# ABC_proto.net
KiCad netlist of a schematic drawn in EAGLE
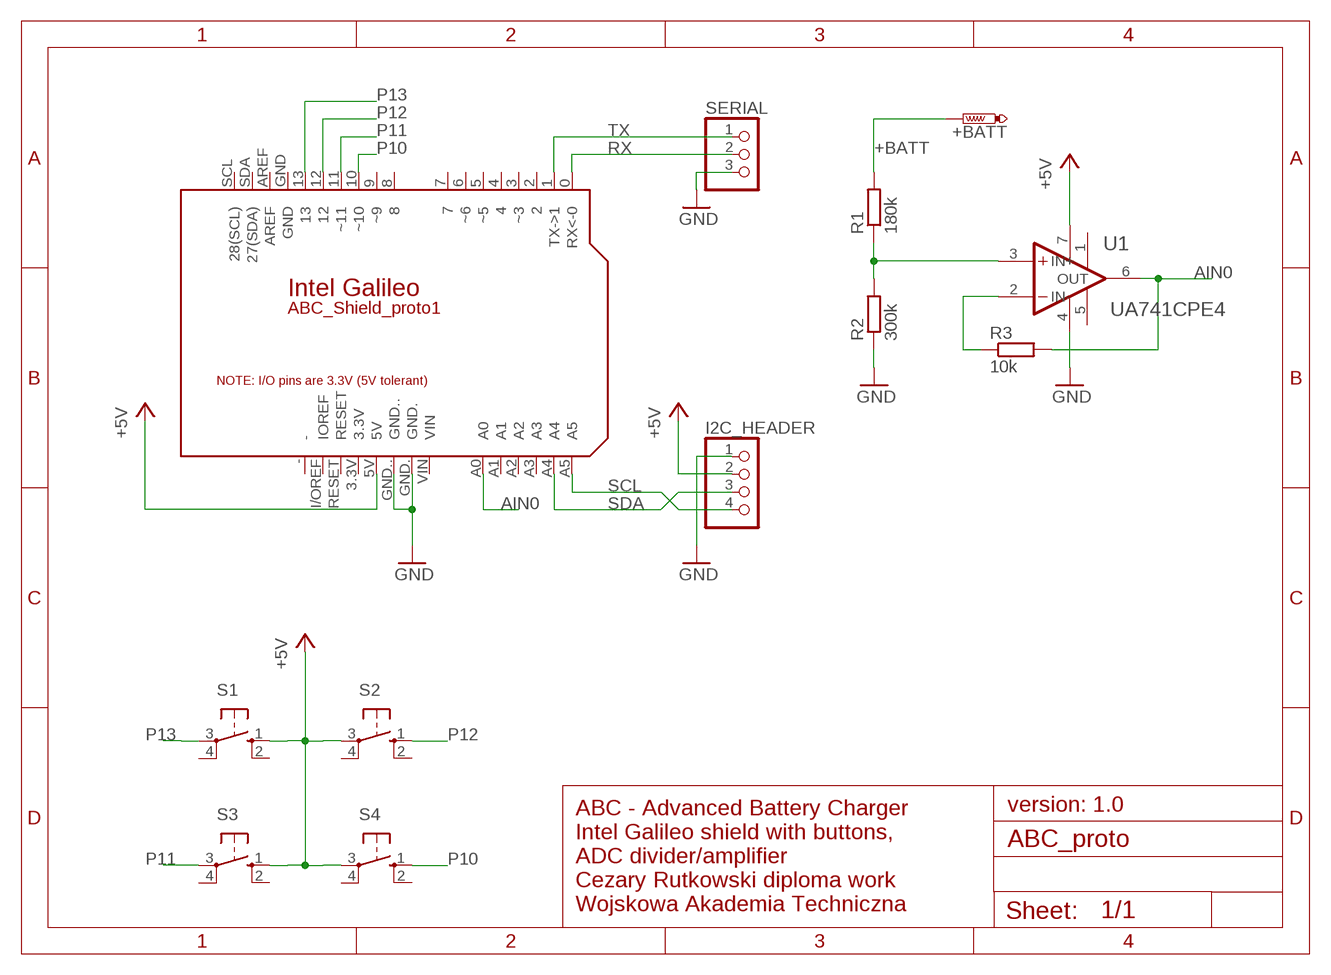
[diagram p0: schematic, sheet 1]

(export (version "E")
  (design (tool "Eeschema 10.0.6"))
  (components
    (comp (ref "+BATT")
      (value "PTR1PAD1-20Y")
      (footprint "eagle-import:P1-20Y")
      (libsource (lib "eagle-import") (part "PTR1PAD1-20Y"))
    )
    (comp (ref "I2C_HEADER")
      (value "PINHD-1X4")
      (footprint "eagle-import:1X04")
      (libsource (lib "eagle-import") (part "PINHD-1X4"))
    )
    (comp (ref "PCB1")
      (value "ARDUINO_101")
      (footprint "eagle-import:ARDUINO_GALILEO")
      (libsource (lib "eagle-import") (part "ARDUINO_101"))
    )
    (comp (ref "R1")
      (value "180k")
      (footprint "eagle-import:0204_5")
      (libsource (lib "eagle-import") (part "R-EU_0204/5"))
    )
    (comp (ref "R2")
      (value "300k")
      (footprint "eagle-import:0204_5")
      (libsource (lib "eagle-import") (part "R-EU_0204/5"))
    )
    (comp (ref "R3")
      (value "10k")
      (footprint "eagle-import:0204_5")
      (libsource (lib "eagle-import") (part "R-EU_0204/5"))
    )
    (comp (ref "S1")
      (value "10-XX")
      (footprint "eagle-import:B3F-10XX")
      (fields (field (name "MPN") "B3F-1000"))
      (libsource (lib "eagle-import") (part "10-XX"))
    )
    (comp (ref "S2")
      (value "10-XX")
      (footprint "eagle-import:B3F-10XX")
      (fields (field (name "MPN") "B3F-1000"))
      (libsource (lib "eagle-import") (part "10-XX"))
    )
    (comp (ref "S3")
      (value "10-XX")
      (footprint "eagle-import:B3F-10XX")
      (fields (field (name "MPN") "B3F-1000"))
      (libsource (lib "eagle-import") (part "10-XX"))
    )
    (comp (ref "S4")
      (value "10-XX")
      (footprint "eagle-import:B3F-10XX")
      (fields (field (name "MPN") "B3F-1000"))
      (libsource (lib "eagle-import") (part "10-XX"))
    )
    (comp (ref "SERIAL")
      (value "PINHD-1X3")
      (footprint "eagle-import:1X03")
      (libsource (lib "eagle-import") (part "PINHD-1X3"))
    )
    (comp (ref "U1")
      (value "UA741CPE4")
      (footprint "eagle-import:DIP254P762X508-8")
      (libsource (lib "eagle-import") (part "UA741CPE4"))
    )
  )
  (nets
    (net (code "1") (name "+5V") (class "Default")
      (node (ref "I2C_HEADER") (pin "2") (pinfunction "2_2") (pintype "passive"))
      (node (ref "PCB1") (pin "5V") (pinfunction "5V_5V") (pintype "bidirectional"))
      (node (ref "S1") (pin "1") (pinfunction "S_1") (pintype "passive"))
      (node (ref "S2") (pin "3") (pinfunction "P_3") (pintype "passive"))
      (node (ref "S3") (pin "1") (pinfunction "S_1") (pintype "passive"))
      (node (ref "S4") (pin "3") (pinfunction "P_3") (pintype "passive"))
      (node (ref "U1") (pin "7") (pinfunction "VCC+_7") (pintype "power_in"))
    )
    (net (code "2") (name "/+BATT") (class "Default")
      (node (ref "+BATT") (pin "TP") (pinfunction "TP_TP") (pintype "input"))
      (node (ref "R1") (pin "2") (pinfunction "2_2") (pintype "passive"))
    )
    (net (code "3") (name "/AIN0") (class "Default")
      (node (ref "PCB1") (pin "A0") (pinfunction "A0_A0") (pintype "bidirectional"))
      (node (ref "R3") (pin "2") (pinfunction "2_2") (pintype "passive"))
      (node (ref "U1") (pin "6") (pinfunction "OUT_6") (pintype "output"))
    )
    (net (code "4") (name "/P10") (class "Default")
      (node (ref "PCB1") (pin "10") (pinfunction "~{10}_10") (pintype "bidirectional"))
      (node (ref "S4") (pin "1") (pinfunction "S_1") (pintype "passive"))
    )
    (net (code "5") (name "/P11") (class "Default")
      (node (ref "PCB1") (pin "11") (pinfunction "~{11}_11") (pintype "bidirectional"))
      (node (ref "S3") (pin "3") (pinfunction "P_3") (pintype "passive"))
    )
    (net (code "6") (name "/P12") (class "Default")
      (node (ref "PCB1") (pin "12") (pinfunction "12_12") (pintype "bidirectional"))
      (node (ref "S2") (pin "1") (pinfunction "S_1") (pintype "passive"))
    )
    (net (code "7") (name "/P13") (class "Default")
      (node (ref "PCB1") (pin "13") (pinfunction "13_13") (pintype "bidirectional"))
      (node (ref "S1") (pin "3") (pinfunction "P_3") (pintype "passive"))
    )
    (net (code "8") (name "/RX") (class "Default")
      (node (ref "PCB1") (pin "0") (pinfunction "RX<-0_0") (pintype "bidirectional"))
      (node (ref "SERIAL") (pin "2") (pinfunction "2_2") (pintype "passive"))
    )
    (net (code "9") (name "/SCL") (class "Default")
      (node (ref "I2C_HEADER") (pin "4") (pinfunction "4_4") (pintype "passive"))
      (node (ref "PCB1") (pin "A5") (pinfunction "A5_A5") (pintype "bidirectional"))
    )
    (net (code "10") (name "/SDA") (class "Default")
      (node (ref "I2C_HEADER") (pin "3") (pinfunction "3_3") (pintype "passive"))
      (node (ref "PCB1") (pin "A4") (pinfunction "A4_A4") (pintype "bidirectional"))
    )
    (net (code "11") (name "/TX") (class "Default")
      (node (ref "PCB1") (pin "1") (pinfunction "TX->1_1") (pintype "bidirectional"))
      (node (ref "SERIAL") (pin "1") (pinfunction "1_1") (pintype "passive"))
    )
    (net (code "12") (name "GND") (class "Default")
      (node (ref "I2C_HEADER") (pin "1") (pinfunction "1_1") (pintype "passive"))
      (node (ref "PCB1") (pin "GND.") (pinfunction "GND._GND.") (pintype "bidirectional"))
      (node (ref "PCB1") (pin "GND..") (pinfunction "GND.._GND..") (pintype "bidirectional"))
      (node (ref "R2") (pin "1") (pinfunction "1_1") (pintype "passive"))
      (node (ref "SERIAL") (pin "3") (pinfunction "3_3") (pintype "passive"))
      (node (ref "U1") (pin "4") (pinfunction "VCC-_4") (pintype "power_in"))
    )
    (net (code "13") (name "Net-(U1-IN+)") (class "Default")
      (node (ref "R1") (pin "1") (pinfunction "1_1") (pintype "passive"))
      (node (ref "R2") (pin "2") (pinfunction "2_2") (pintype "passive"))
      (node (ref "U1") (pin "3") (pinfunction "IN+_3") (pintype "input"))
    )
    (net (code "14") (name "Net-(U1-IN-)") (class "Default")
      (node (ref "R3") (pin "1") (pinfunction "1_1") (pintype "passive"))
      (node (ref "U1") (pin "2") (pinfunction "IN-_2") (pintype "input"))
    )
    (net (code "15") (name "unconnected-(PCB1-27(SDA)-PadSDA)") (class "Default")
      (node (ref "PCB1") (pin "SDA") (pinfunction "27(SDA)_SDA") (pintype "bidirectional"))
    )
    (net (code "16") (name "unconnected-(PCB1-28(SCL)-PadSCL)") (class "Default")
      (node (ref "PCB1") (pin "SCL") (pinfunction "28(SCL)_SCL") (pintype "bidirectional"))
    )
    (net (code "17") (name "unconnected-(PCB1-IOREF-PadI{slash}OREF)") (class "Default")
      (node (ref "PCB1") (pin "I/OREF") (pinfunction "IOREF_I/OREF") (pintype "bidirectional"))
    )
    (net (code "18") (name "unconnected-(PCB1-Pad-)") (class "Default")
      (node (ref "PCB1") (pin "-") (pinfunction "-_-") (pintype "bidirectional"))
    )
    (net (code "19") (name "unconnected-(PCB1-Pad2)") (class "Default")
      (node (ref "PCB1") (pin "2") (pinfunction "2_2") (pintype "bidirectional"))
    )
    (net (code "20") (name "unconnected-(PCB1-Pad3.3V)") (class "Default")
      (node (ref "PCB1") (pin "3.3V") (pinfunction "3.3V_3.3V") (pintype "bidirectional"))
    )
    (net (code "21") (name "unconnected-(PCB1-Pad4)") (class "Default")
      (node (ref "PCB1") (pin "4") (pinfunction "4_4") (pintype "bidirectional"))
    )
    (net (code "22") (name "unconnected-(PCB1-Pad7)") (class "Default")
      (node (ref "PCB1") (pin "7") (pinfunction "7_7") (pintype "bidirectional"))
    )
    (net (code "23") (name "unconnected-(PCB1-Pad8)") (class "Default")
      (node (ref "PCB1") (pin "8") (pinfunction "8_8") (pintype "bidirectional"))
    )
    (net (code "24") (name "unconnected-(PCB1-PadA1)") (class "Default")
      (node (ref "PCB1") (pin "A1") (pinfunction "A1_A1") (pintype "bidirectional"))
    )
    (net (code "25") (name "unconnected-(PCB1-PadA2)") (class "Default")
      (node (ref "PCB1") (pin "A2") (pinfunction "A2_A2") (pintype "bidirectional"))
    )
    (net (code "26") (name "unconnected-(PCB1-PadA3)") (class "Default")
      (node (ref "PCB1") (pin "A3") (pinfunction "A3_A3") (pintype "bidirectional"))
    )
    (net (code "27") (name "unconnected-(PCB1-PadAREF)") (class "Default")
      (node (ref "PCB1") (pin "AREF") (pinfunction "AREF_AREF") (pintype "bidirectional"))
    )
    (net (code "28") (name "unconnected-(PCB1-PadGND)") (class "Default")
      (node (ref "PCB1") (pin "GND") (pinfunction "GND_GND") (pintype "bidirectional"))
    )
    (net (code "29") (name "unconnected-(PCB1-PadRESET)") (class "Default")
      (node (ref "PCB1") (pin "RESET") (pinfunction "RESET_RESET") (pintype "bidirectional"))
    )
    (net (code "30") (name "unconnected-(PCB1-PadVIN)") (class "Default")
      (node (ref "PCB1") (pin "VIN") (pinfunction "VIN_VIN") (pintype "bidirectional"))
    )
    (net (code "31") (name "unconnected-(PCB1-~{3}-Pad3)") (class "Default")
      (node (ref "PCB1") (pin "3") (pinfunction "~{3}_3") (pintype "bidirectional"))
    )
    (net (code "32") (name "unconnected-(PCB1-~{5}-Pad5)") (class "Default")
      (node (ref "PCB1") (pin "5") (pinfunction "~{5}_5") (pintype "bidirectional"))
    )
    (net (code "33") (name "unconnected-(PCB1-~{6}-Pad6)") (class "Default")
      (node (ref "PCB1") (pin "6") (pinfunction "~{6}_6") (pintype "bidirectional"))
    )
    (net (code "34") (name "unconnected-(PCB1-~{9}-Pad9)") (class "Default")
      (node (ref "PCB1") (pin "9") (pinfunction "~{9}_9") (pintype "bidirectional"))
    )
    (net (code "35") (name "unconnected-(S1-P1-Pad4)") (class "Default")
      (node (ref "S1") (pin "4") (pinfunction "P1_4") (pintype "passive"))
    )
    (net (code "36") (name "unconnected-(S1-S1-Pad2)") (class "Default")
      (node (ref "S1") (pin "2") (pinfunction "S1_2") (pintype "passive"))
    )
    (net (code "37") (name "unconnected-(S2-P1-Pad4)") (class "Default")
      (node (ref "S2") (pin "4") (pinfunction "P1_4") (pintype "passive"))
    )
    (net (code "38") (name "unconnected-(S2-S1-Pad2)") (class "Default")
      (node (ref "S2") (pin "2") (pinfunction "S1_2") (pintype "passive"))
    )
    (net (code "39") (name "unconnected-(S3-P1-Pad4)") (class "Default")
      (node (ref "S3") (pin "4") (pinfunction "P1_4") (pintype "passive"))
    )
    (net (code "40") (name "unconnected-(S3-S1-Pad2)") (class "Default")
      (node (ref "S3") (pin "2") (pinfunction "S1_2") (pintype "passive"))
    )
    (net (code "41") (name "unconnected-(S4-P1-Pad4)") (class "Default")
      (node (ref "S4") (pin "4") (pinfunction "P1_4") (pintype "passive"))
    )
    (net (code "42") (name "unconnected-(S4-S1-Pad2)") (class "Default")
      (node (ref "S4") (pin "2") (pinfunction "S1_2") (pintype "passive"))
    )
    (net (code "43") (name "unconnected-(U1-OFS_N1-Pad1)") (class "Default")
      (node (ref "U1") (pin "1") (pinfunction "OFS_N1_1") (pintype "input"))
    )
    (net (code "44") (name "unconnected-(U1-OFS_N2-Pad5)") (class "Default")
      (node (ref "U1") (pin "5") (pinfunction "OFS_N2_5") (pintype "input"))
    )
  )
)
